# main.net
KiCad netlist of a schematic drawn in EAGLE
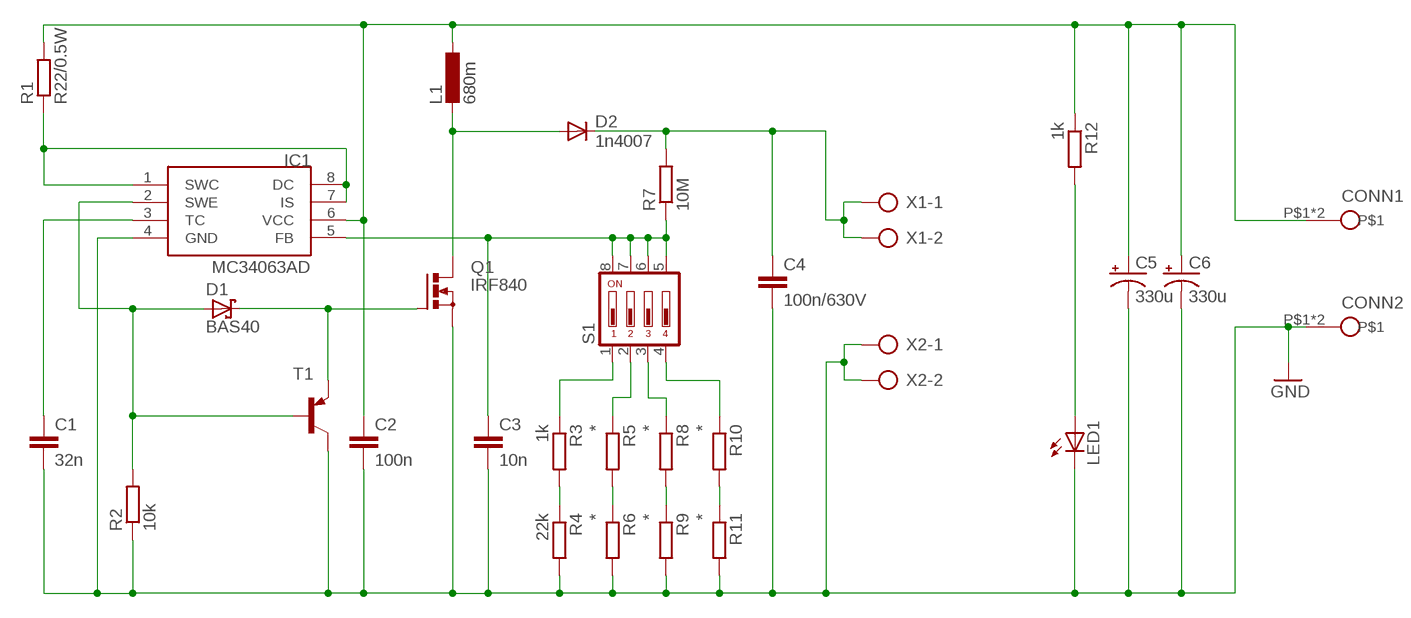
[diagram p0: schematic, sheet 1]

(export (version "E")
  (design (tool "Eeschema 10.0.6"))
  (components
    (comp (ref "11")
      (value "BANANA-PLUG-2-PADS")
      (footprint "eagle-import:BANANA-PLUG-2-PADS")
      (fields (field (name "PREFIX") "CONN1"))
      (libsource (lib "eagle-import") (part "BANANA-PLUG-2-PADS"))
    )
    (comp (ref "12")
      (value "BANANA-PLUG-2-PADS")
      (footprint "eagle-import:BANANA-PLUG-2-PADS")
      (fields (field (name "PREFIX") "CONN2"))
      (libsource (lib "eagle-import") (part "BANANA-PLUG-2-PADS"))
    )
    (comp (ref "C1")
      (value "32n")
      (footprint "eagle-import:C025-025X050")
      (libsource (lib "eagle-import") (part "C-EU025-025X050"))
    )
    (comp (ref "C2")
      (value "100n")
      (footprint "eagle-import:C3216")
      (libsource (lib "eagle-import") (part "C-EUC3216"))
    )
    (comp (ref "C3")
      (value "10n")
      (footprint "eagle-import:C3216")
      (libsource (lib "eagle-import") (part "C-EUC3216"))
    )
    (comp (ref "C4")
      (value "100n/630V")
      (footprint "eagle-import:C102-064X133")
      (libsource (lib "eagle-import") (part "C-EU102-064X133"))
    )
    (comp (ref "C5")
      (value "330u")
      (footprint "eagle-import:A_3216-18W")
      (libsource (lib "eagle-import") (part "CPOL-USA/3216-18W"))
    )
    (comp (ref "C6")
      (value "330u")
      (footprint "eagle-import:A_3216-18W")
      (libsource (lib "eagle-import") (part "CPOL-USA/3216-18W"))
    )
    (comp (ref "D1")
      (value "BAS40")
      (footprint "eagle-import:SOT23")
      (libsource (lib "eagle-import") (part "BAS40"))
    )
    (comp (ref "D2")
      (value "1n4007")
      (footprint "eagle-import:DO41-10")
      (libsource (lib "eagle-import") (part "1N4004"))
    )
    (comp (ref "IC1")
      (value "MC34063AD")
      (footprint "eagle-import:SOIC8")
      (libsource (lib "eagle-import") (part "MC34063AD"))
    )
    (comp (ref "L1")
      (value "680m")
      (footprint "eagle-import:0207_5V")
      (libsource (lib "eagle-import") (part "L-EU0207/5V"))
    )
    (comp (ref "LED1")
      (value "LED3MM")
      (footprint "eagle-import:LED3MM")
      (libsource (lib "eagle-import") (part "LED3MM"))
    )
    (comp (ref "Q1")
      (value "IRF840")
      (footprint "eagle-import:TO220BV")
      (libsource (lib "eagle-import") (part "BUZ11BV"))
    )
    (comp (ref "R1")
      (value "R22/0.5W")
      (footprint "eagle-import:0207_5V")
      (libsource (lib "eagle-import") (part "R-EU_0207/5V"))
    )
    (comp (ref "R2")
      (value "10k")
      (footprint "eagle-import:R1206")
      (libsource (lib "eagle-import") (part "R-EU_R1206"))
    )
    (comp (ref "R3")
      (value "1k")
      (footprint "eagle-import:R1206")
      (libsource (lib "eagle-import") (part "R-EU_R1206"))
    )
    (comp (ref "R4")
      (value "22k")
      (footprint "eagle-import:R1206")
      (libsource (lib "eagle-import") (part "R-EU_R1206"))
    )
    (comp (ref "R5")
      (value "*")
      (footprint "eagle-import:R1206")
      (libsource (lib "eagle-import") (part "R-EU_R1206"))
    )
    (comp (ref "R6")
      (value "*")
      (footprint "eagle-import:R1206")
      (libsource (lib "eagle-import") (part "R-EU_R1206"))
    )
    (comp (ref "R7")
      (value "10M")
      (footprint "eagle-import:0207_5V")
      (libsource (lib "eagle-import") (part "R-EU_0207/5V"))
    )
    (comp (ref "R8")
      (value "*")
      (footprint "eagle-import:R1206")
      (libsource (lib "eagle-import") (part "R-EU_R1206"))
    )
    (comp (ref "R9")
      (value "*")
      (footprint "eagle-import:R1206")
      (libsource (lib "eagle-import") (part "R-EU_R1206"))
    )
    (comp (ref "R10")
      (value "*")
      (footprint "eagle-import:R1206")
      (libsource (lib "eagle-import") (part "R-EU_R1206"))
    )
    (comp (ref "R11")
      (value "*")
      (footprint "eagle-import:R1206")
      (libsource (lib "eagle-import") (part "R-EU_R1206"))
    )
    (comp (ref "R12")
      (value "1k")
      (footprint "eagle-import:R1206")
      (libsource (lib "eagle-import") (part "R-EU_R1206"))
    )
    (comp (ref "S1")
      (value "DS04")
      (footprint "eagle-import:DS-04")
      (libsource (lib "eagle-import") (part "DS04"))
    )
    (comp (ref "T1")
      (value "BC807-40-PNP-SOT23-BEC")
      (footprint "eagle-import:SOT23-BEC")
      (libsource (lib "eagle-import") (part "-PNP-SOT23-BECBC807-40"))
    )
    (comp (ref "X1")
      (value "AK500/2-H")
      (footprint "eagle-import:AK500_2-H")
      (libsource (lib "eagle-import") (part "AK500/2-H"))
    )
    (comp (ref "X2")
      (value "AK500/2-H")
      (footprint "eagle-import:AK500_2-H")
      (libsource (lib "eagle-import") (part "AK500/2-H"))
    )
  )
  (nets
    (net (code "1") (name "GND") (class "Default")
      (node (ref "12") (pin "P$1") (pinfunction "P$1_P$1") (pintype "bidirectional"))
      (node (ref "12") (pin "P$2") (pinfunction "P$1_P$2") (pintype "bidirectional"))
      (node (ref "C1") (pin "2") (pinfunction "2_2") (pintype "passive"))
      (node (ref "C2") (pin "2") (pinfunction "2_2") (pintype "passive"))
      (node (ref "C3") (pin "2") (pinfunction "2_2") (pintype "passive"))
      (node (ref "C4") (pin "2") (pinfunction "2_2") (pintype "passive"))
      (node (ref "C5") (pin "-") (pinfunction "-_-") (pintype "passive"))
      (node (ref "C6") (pin "-") (pinfunction "-_-") (pintype "passive"))
      (node (ref "IC1") (pin "4") (pinfunction "GND_4") (pintype "passive"))
      (node (ref "LED1") (pin "K") (pinfunction "C_K") (pintype "passive"))
      (node (ref "Q1") (pin "S") (pinfunction "S_S") (pintype "passive"))
      (node (ref "R11") (pin "2") (pinfunction "2_2") (pintype "passive"))
      (node (ref "R2") (pin "1") (pinfunction "1_1") (pintype "passive"))
      (node (ref "R4") (pin "2") (pinfunction "2_2") (pintype "passive"))
      (node (ref "R6") (pin "2") (pinfunction "2_2") (pintype "passive"))
      (node (ref "R9") (pin "2") (pinfunction "2_2") (pintype "passive"))
      (node (ref "T1") (pin "C") (pinfunction "C_C") (pintype "passive"))
      (node (ref "X2") (pin "1") (pinfunction "KL_1") (pintype "passive"))
      (node (ref "X2") (pin "2") (pinfunction "KL_2") (pintype "passive"))
    )
    (net (code "2") (name "Net-(D1-A)") (class "Default")
      (node (ref "D1") (pin "1") (pinfunction "A_1") (pintype "passive"))
      (node (ref "IC1") (pin "2") (pinfunction "SWE_2") (pintype "passive"))
      (node (ref "R2") (pin "2") (pinfunction "2_2") (pintype "passive"))
      (node (ref "T1") (pin "B") (pinfunction "B_B") (pintype "passive"))
    )
    (net (code "3") (name "Net-(D1-C)") (class "Default")
      (node (ref "D1") (pin "3") (pinfunction "C_3") (pintype "passive"))
      (node (ref "Q1") (pin "G") (pinfunction "G_G") (pintype "passive"))
      (node (ref "T1") (pin "E") (pinfunction "E_E") (pintype "passive"))
    )
    (net (code "4") (name "Net-(D2-PadA)") (class "Default")
      (node (ref "D2") (pin "A") (pinfunction "A_A") (pintype "passive"))
      (node (ref "L1") (pin "2") (pinfunction "2_2") (pintype "passive"))
      (node (ref "Q1") (pin "D") (pinfunction "D_D") (pintype "passive"))
    )
    (net (code "5") (name "Net-(IC1-DC)") (class "Default")
      (node (ref "IC1") (pin "1") (pinfunction "SWC_1") (pintype "passive"))
      (node (ref "IC1") (pin "7") (pinfunction "IS_7") (pintype "passive"))
      (node (ref "IC1") (pin "8") (pinfunction "DC_8") (pintype "passive"))
      (node (ref "R1") (pin "1") (pinfunction "1_1") (pintype "passive"))
    )
    (net (code "6") (name "Net-(IC1-FB)") (class "Default")
      (node (ref "C3") (pin "1") (pinfunction "1_1") (pintype "passive"))
      (node (ref "IC1") (pin "5") (pinfunction "FB_5") (pintype "passive"))
      (node (ref "R7") (pin "1") (pinfunction "1_1") (pintype "passive"))
      (node (ref "S1") (pin "5") (pinfunction "5_5") (pintype "passive"))
      (node (ref "S1") (pin "6") (pinfunction "6_6") (pintype "passive"))
      (node (ref "S1") (pin "7") (pinfunction "7_7") (pintype "passive"))
      (node (ref "S1") (pin "8") (pinfunction "8_8") (pintype "passive"))
    )
    (net (code "7") (name "Net-(IC1-TC)") (class "Default")
      (node (ref "C1") (pin "1") (pinfunction "1_1") (pintype "passive"))
      (node (ref "IC1") (pin "3") (pinfunction "TC_3") (pintype "passive"))
    )
    (net (code "8") (name "Net-(IC1-VCC)") (class "Default")
      (node (ref "11") (pin "P$1") (pinfunction "P$1_P$1") (pintype "bidirectional"))
      (node (ref "11") (pin "P$2") (pinfunction "P$1_P$2") (pintype "bidirectional"))
      (node (ref "C2") (pin "1") (pinfunction "1_1") (pintype "passive"))
      (node (ref "C5") (pin "+") (pinfunction "+_+") (pintype "passive"))
      (node (ref "C6") (pin "+") (pinfunction "+_+") (pintype "passive"))
      (node (ref "IC1") (pin "6") (pinfunction "VCC_6") (pintype "passive"))
      (node (ref "L1") (pin "1") (pinfunction "1_1") (pintype "passive"))
      (node (ref "R1") (pin "2") (pinfunction "2_2") (pintype "passive"))
      (node (ref "R12") (pin "1") (pinfunction "1_1") (pintype "passive"))
    )
    (net (code "9") (name "Net-(LED1-PadA)") (class "Default")
      (node (ref "LED1") (pin "A") (pinfunction "A_A") (pintype "passive"))
      (node (ref "R12") (pin "2") (pinfunction "2_2") (pintype "passive"))
    )
    (net (code "10") (name "Net-(R3-Pad1)") (class "Default")
      (node (ref "R3") (pin "1") (pinfunction "1_1") (pintype "passive"))
      (node (ref "S1") (pin "1") (pinfunction "1_1") (pintype "passive"))
    )
    (net (code "11") (name "Net-(R3-Pad2)") (class "Default")
      (node (ref "R3") (pin "2") (pinfunction "2_2") (pintype "passive"))
      (node (ref "R4") (pin "1") (pinfunction "1_1") (pintype "passive"))
    )
    (net (code "12") (name "Net-(R5-Pad1)") (class "Default")
      (node (ref "R5") (pin "1") (pinfunction "1_1") (pintype "passive"))
      (node (ref "S1") (pin "2") (pinfunction "2_2") (pintype "passive"))
    )
    (net (code "13") (name "Net-(R5-Pad2)") (class "Default")
      (node (ref "R5") (pin "2") (pinfunction "2_2") (pintype "passive"))
      (node (ref "R6") (pin "1") (pinfunction "1_1") (pintype "passive"))
    )
    (net (code "14") (name "Net-(R8-Pad1)") (class "Default")
      (node (ref "R8") (pin "1") (pinfunction "1_1") (pintype "passive"))
      (node (ref "S1") (pin "3") (pinfunction "3_3") (pintype "passive"))
    )
    (net (code "15") (name "Net-(R8-Pad2)") (class "Default")
      (node (ref "R8") (pin "2") (pinfunction "2_2") (pintype "passive"))
      (node (ref "R9") (pin "1") (pinfunction "1_1") (pintype "passive"))
    )
    (net (code "16") (name "Net-(R10-Pad1)") (class "Default")
      (node (ref "R10") (pin "1") (pinfunction "1_1") (pintype "passive"))
      (node (ref "S1") (pin "4") (pinfunction "4_4") (pintype "passive"))
    )
    (net (code "17") (name "Net-(R10-Pad2)") (class "Default")
      (node (ref "R10") (pin "2") (pinfunction "2_2") (pintype "passive"))
      (node (ref "R11") (pin "1") (pinfunction "1_1") (pintype "passive"))
    )
    (net (code "18") (name "Net-(X1A-KL)") (class "Default")
      (node (ref "C4") (pin "1") (pinfunction "1_1") (pintype "passive"))
      (node (ref "D2") (pin "C") (pinfunction "C_C") (pintype "passive"))
      (node (ref "R7") (pin "2") (pinfunction "2_2") (pintype "passive"))
      (node (ref "X1") (pin "1") (pinfunction "KL_1") (pintype "passive"))
      (node (ref "X1") (pin "2") (pinfunction "KL_2") (pintype "passive"))
    )
  )
)
